# BatteryBoard.net
KiCad netlist of a schematic drawn in EAGLE
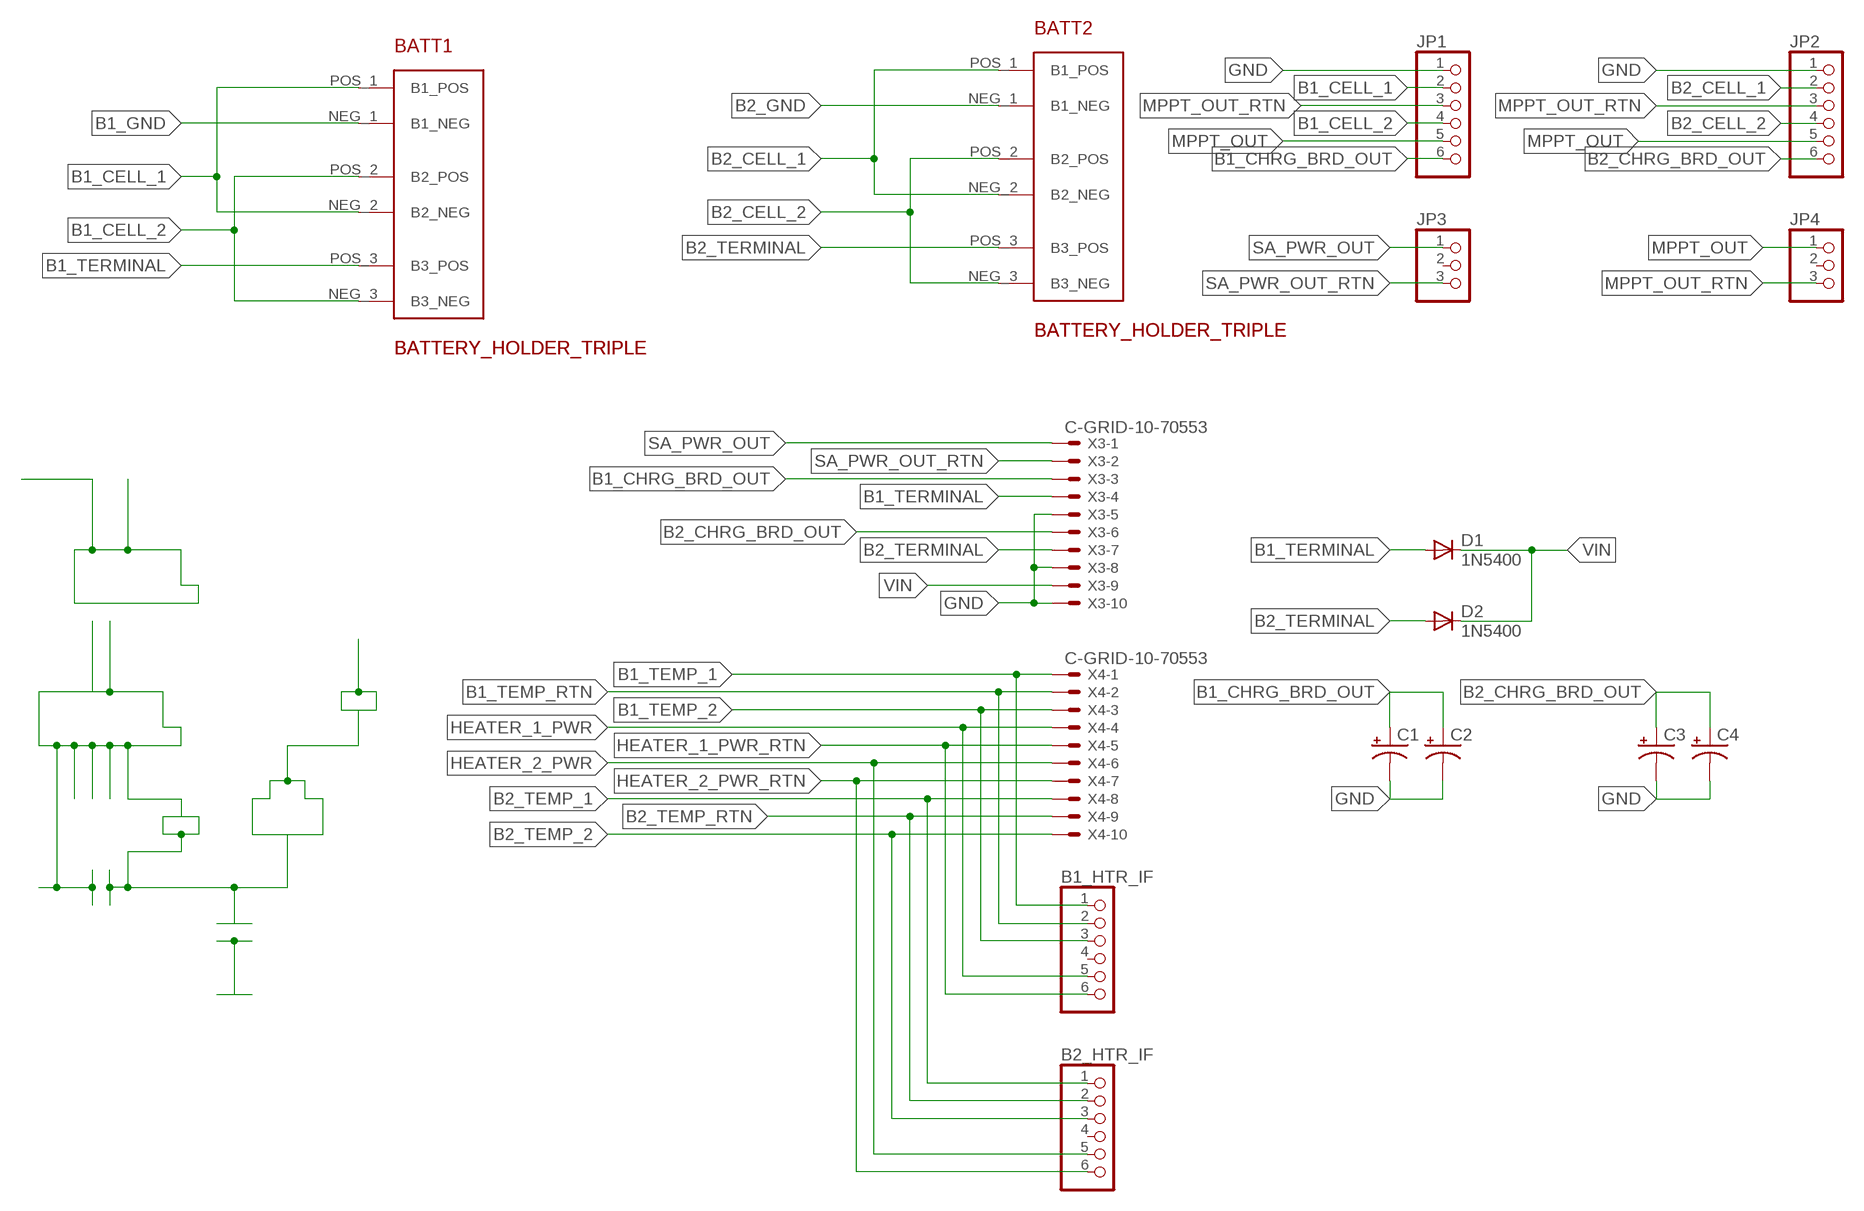
[diagram p0: schematic, sheet 1]

(export (version "E")
  (design (tool "Eeschema 10.0.6"))
  (components
    (comp (ref "B1_HTR_IF")
      (value "PINHD-1X6CLEAN")
      (footprint "eagle-import:1X06-CLEAN")
      (libsource (lib "eagle-import") (part "PINHD-1X6CLEAN"))
    )
    (comp (ref "B2_HTR_IF")
      (value "PINHD-1X6CLEAN")
      (footprint "eagle-import:1X06-CLEAN")
      (libsource (lib "eagle-import") (part "PINHD-1X6CLEAN"))
    )
    (comp (ref "BATT1")
      (value "BATTERY_HOLDER_TRIPLE")
      (footprint "eagle-import:BATT_HOLDER_SINGLE")
      (libsource (lib "eagle-import") (part "BATTERY_HOLDER_TRIPLE"))
    )
    (comp (ref "BATT2")
      (value "BATTERY_HOLDER_TRIPLE")
      (footprint "eagle-import:BATT_HOLDER_SINGLE")
      (libsource (lib "eagle-import") (part "BATTERY_HOLDER_TRIPLE"))
    )
    (comp (ref "C1")
      (value "CPOL-USCT7343")
      (footprint "eagle-import:CT7343")
      (libsource (lib "eagle-import") (part "CPOL-USCT7343"))
    )
    (comp (ref "C2")
      (value "CPOL-USCT7343")
      (footprint "eagle-import:CT7343")
      (libsource (lib "eagle-import") (part "CPOL-USCT7343"))
    )
    (comp (ref "C3")
      (value "CPOL-USCT7343")
      (footprint "eagle-import:CT7343")
      (libsource (lib "eagle-import") (part "CPOL-USCT7343"))
    )
    (comp (ref "C4")
      (value "CPOL-USCT7343")
      (footprint "eagle-import:CT7343")
      (libsource (lib "eagle-import") (part "CPOL-USCT7343"))
    )
    (comp (ref "D1")
      (value "1N5400")
      (footprint "eagle-import:DO201-15")
      (libsource (lib "eagle-import") (part "1N5400"))
    )
    (comp (ref "D2")
      (value "1N5400")
      (footprint "eagle-import:DO201-15")
      (libsource (lib "eagle-import") (part "1N5400"))
    )
    (comp (ref "JP1")
      (value "PINHD-1X6CLEAN")
      (footprint "eagle-import:1X06-CLEAN")
      (libsource (lib "eagle-import") (part "PINHD-1X6CLEAN"))
    )
    (comp (ref "JP2")
      (value "PINHD-1X6CLEAN")
      (footprint "eagle-import:1X06-CLEAN")
      (libsource (lib "eagle-import") (part "PINHD-1X6CLEAN"))
    )
    (comp (ref "JP3")
      (value "PINHD-1X3")
      (footprint "eagle-import:1X03")
      (libsource (lib "eagle-import") (part "PINHD-1X3"))
    )
    (comp (ref "JP4")
      (value "PINHD-1X3")
      (footprint "eagle-import:1X03")
      (libsource (lib "eagle-import") (part "PINHD-1X3"))
    )
    (comp (ref "X3")
      (value "C-GRID-10-70553")
      (footprint "eagle-import:70553-10")
      (libsource (lib "eagle-import") (part "C-GRID-10-70553"))
    )
    (comp (ref "X4")
      (value "C-GRID-10-70553")
      (footprint "eagle-import:70553-10")
      (libsource (lib "eagle-import") (part "C-GRID-10-70553"))
    )
  )
  (nets
    (net (code "1") (name "B1_CELL_1") (class "Default")
      (node (ref "BATT1") (pin "NEG_2") (pinfunction "B2_NEG_NEG_2") (pintype "bidirectional"))
      (node (ref "BATT1") (pin "POS_1") (pinfunction "B1_POS_POS_1") (pintype "bidirectional"))
      (node (ref "JP1") (pin "2") (pinfunction "2_2") (pintype "passive"))
    )
    (net (code "2") (name "B1_CELL_2") (class "Default")
      (node (ref "BATT1") (pin "NEG_3") (pinfunction "B3_NEG_NEG_3") (pintype "bidirectional"))
      (node (ref "BATT1") (pin "POS_2") (pinfunction "B2_POS_POS_2") (pintype "bidirectional"))
      (node (ref "JP1") (pin "4") (pinfunction "4_4") (pintype "passive"))
    )
    (net (code "3") (name "B1_CHRG_BRD_OUT") (class "Default")
      (node (ref "C1") (pin "+") (pinfunction "+_+") (pintype "passive"))
      (node (ref "C2") (pin "+") (pinfunction "+_+") (pintype "passive"))
      (node (ref "JP1") (pin "6") (pinfunction "6_6") (pintype "passive"))
      (node (ref "X3") (pin "3") (pinfunction "S_3") (pintype "passive"))
    )
    (net (code "4") (name "B1_GND") (class "Default")
      (node (ref "BATT1") (pin "NEG_1") (pinfunction "B1_NEG_NEG_1") (pintype "bidirectional"))
    )
    (net (code "5") (name "B1_TEMP_1") (class "Default")
      (node (ref "B1_HTR_IF") (pin "1") (pinfunction "1_1") (pintype "passive"))
      (node (ref "X4") (pin "1") (pinfunction "S_1") (pintype "passive"))
    )
    (net (code "6") (name "B1_TEMP_2") (class "Default")
      (node (ref "B1_HTR_IF") (pin "3") (pinfunction "3_3") (pintype "passive"))
      (node (ref "X4") (pin "3") (pinfunction "S_3") (pintype "passive"))
    )
    (net (code "7") (name "B1_TEMP_RTN") (class "Default")
      (node (ref "B1_HTR_IF") (pin "2") (pinfunction "2_2") (pintype "passive"))
      (node (ref "X4") (pin "2") (pinfunction "S_2") (pintype "passive"))
    )
    (net (code "8") (name "B1_TERMINAL") (class "Default")
      (node (ref "BATT1") (pin "POS_3") (pinfunction "B3_POS_POS_3") (pintype "bidirectional"))
      (node (ref "D1") (pin "A") (pinfunction "A_A") (pintype "passive"))
      (node (ref "X3") (pin "4") (pinfunction "S_4") (pintype "passive"))
    )
    (net (code "9") (name "B2_CELL_1") (class "Default")
      (node (ref "BATT2") (pin "NEG_2") (pinfunction "B2_NEG_NEG_2") (pintype "bidirectional"))
      (node (ref "BATT2") (pin "POS_1") (pinfunction "B1_POS_POS_1") (pintype "bidirectional"))
      (node (ref "JP2") (pin "2") (pinfunction "2_2") (pintype "passive"))
    )
    (net (code "10") (name "B2_CELL_2") (class "Default")
      (node (ref "BATT2") (pin "NEG_3") (pinfunction "B3_NEG_NEG_3") (pintype "bidirectional"))
      (node (ref "BATT2") (pin "POS_2") (pinfunction "B2_POS_POS_2") (pintype "bidirectional"))
      (node (ref "JP2") (pin "4") (pinfunction "4_4") (pintype "passive"))
    )
    (net (code "11") (name "B2_CHRG_BRD_OUT") (class "Default")
      (node (ref "C3") (pin "+") (pinfunction "+_+") (pintype "passive"))
      (node (ref "C4") (pin "+") (pinfunction "+_+") (pintype "passive"))
      (node (ref "JP2") (pin "6") (pinfunction "6_6") (pintype "passive"))
      (node (ref "X3") (pin "6") (pinfunction "S_6") (pintype "passive"))
    )
    (net (code "12") (name "B2_GND") (class "Default")
      (node (ref "BATT2") (pin "NEG_1") (pinfunction "B1_NEG_NEG_1") (pintype "bidirectional"))
    )
    (net (code "13") (name "B2_TEMP_1") (class "Default")
      (node (ref "B2_HTR_IF") (pin "1") (pinfunction "1_1") (pintype "passive"))
      (node (ref "X4") (pin "8") (pinfunction "S_8") (pintype "passive"))
    )
    (net (code "14") (name "B2_TEMP_2") (class "Default")
      (node (ref "B2_HTR_IF") (pin "3") (pinfunction "3_3") (pintype "passive"))
      (node (ref "X4") (pin "10") (pinfunction "S_10") (pintype "passive"))
    )
    (net (code "15") (name "B2_TEMP_RTN") (class "Default")
      (node (ref "B2_HTR_IF") (pin "2") (pinfunction "2_2") (pintype "passive"))
      (node (ref "X4") (pin "9") (pinfunction "S_9") (pintype "passive"))
    )
    (net (code "16") (name "B2_TERMINAL") (class "Default")
      (node (ref "BATT2") (pin "POS_3") (pinfunction "B3_POS_POS_3") (pintype "bidirectional"))
      (node (ref "D2") (pin "A") (pinfunction "A_A") (pintype "passive"))
      (node (ref "X3") (pin "7") (pinfunction "S_7") (pintype "passive"))
    )
    (net (code "17") (name "GND") (class "Default")
      (node (ref "C1") (pin "-") (pinfunction "-_-") (pintype "passive"))
      (node (ref "C2") (pin "-") (pinfunction "-_-") (pintype "passive"))
      (node (ref "C3") (pin "-") (pinfunction "-_-") (pintype "passive"))
      (node (ref "C4") (pin "-") (pinfunction "-_-") (pintype "passive"))
      (node (ref "JP1") (pin "1") (pinfunction "1_1") (pintype "passive"))
      (node (ref "JP2") (pin "1") (pinfunction "1_1") (pintype "passive"))
      (node (ref "X3") (pin "10") (pinfunction "S_10") (pintype "passive"))
      (node (ref "X3") (pin "5") (pinfunction "S_5") (pintype "passive"))
      (node (ref "X3") (pin "8") (pinfunction "S_8") (pintype "passive"))
    )
    (net (code "18") (name "HEATER_1_PWR") (class "Default")
      (node (ref "B1_HTR_IF") (pin "5") (pinfunction "5_5") (pintype "passive"))
      (node (ref "X4") (pin "4") (pinfunction "S_4") (pintype "passive"))
    )
    (net (code "19") (name "HEATER_1_PWR_RTN") (class "Default")
      (node (ref "B1_HTR_IF") (pin "6") (pinfunction "6_6") (pintype "passive"))
      (node (ref "X4") (pin "5") (pinfunction "S_5") (pintype "passive"))
    )
    (net (code "20") (name "HEATER_2_PWR") (class "Default")
      (node (ref "B2_HTR_IF") (pin "5") (pinfunction "5_5") (pintype "passive"))
      (node (ref "X4") (pin "6") (pinfunction "S_6") (pintype "passive"))
    )
    (net (code "21") (name "HEATER_2_PWR_RTN") (class "Default")
      (node (ref "B2_HTR_IF") (pin "6") (pinfunction "6_6") (pintype "passive"))
      (node (ref "X4") (pin "7") (pinfunction "S_7") (pintype "passive"))
    )
    (net (code "22") (name "MPPT_OUT") (class "Default")
      (node (ref "JP1") (pin "5") (pinfunction "5_5") (pintype "passive"))
      (node (ref "JP2") (pin "5") (pinfunction "5_5") (pintype "passive"))
      (node (ref "JP4") (pin "1") (pinfunction "1_1") (pintype "passive"))
    )
    (net (code "23") (name "MPPT_OUT_RTN") (class "Default")
      (node (ref "JP1") (pin "3") (pinfunction "3_3") (pintype "passive"))
      (node (ref "JP2") (pin "3") (pinfunction "3_3") (pintype "passive"))
      (node (ref "JP4") (pin "3") (pinfunction "3_3") (pintype "passive"))
    )
    (net (code "24") (name "SA_PWR_OUT") (class "Default")
      (node (ref "JP3") (pin "1") (pinfunction "1_1") (pintype "passive"))
      (node (ref "X3") (pin "1") (pinfunction "S_1") (pintype "passive"))
    )
    (net (code "25") (name "SA_PWR_OUT_RTN") (class "Default")
      (node (ref "JP3") (pin "3") (pinfunction "3_3") (pintype "passive"))
      (node (ref "X3") (pin "2") (pinfunction "S_2") (pintype "passive"))
    )
    (net (code "26") (name "VIN") (class "Default")
      (node (ref "D1") (pin "C") (pinfunction "C_C") (pintype "passive"))
      (node (ref "D2") (pin "C") (pinfunction "C_C") (pintype "passive"))
      (node (ref "X3") (pin "9") (pinfunction "S_9") (pintype "passive"))
    )
    (net (code "27") (name "unconnected-(B1_HTR_IF-Pad4)") (class "Default")
      (node (ref "B1_HTR_IF") (pin "4") (pinfunction "4_4") (pintype "passive"))
    )
    (net (code "28") (name "unconnected-(B2_HTR_IF-Pad4)") (class "Default")
      (node (ref "B2_HTR_IF") (pin "4") (pinfunction "4_4") (pintype "passive"))
    )
    (net (code "29") (name "unconnected-(JP3-Pad2)") (class "Default")
      (node (ref "JP3") (pin "2") (pinfunction "2_2") (pintype "passive"))
    )
    (net (code "30") (name "unconnected-(JP4-Pad2)") (class "Default")
      (node (ref "JP4") (pin "2") (pinfunction "2_2") (pintype "passive"))
    )
  )
)
